# FPGA_IO.net
KiCad netlist of a schematic drawn in Altium Designer
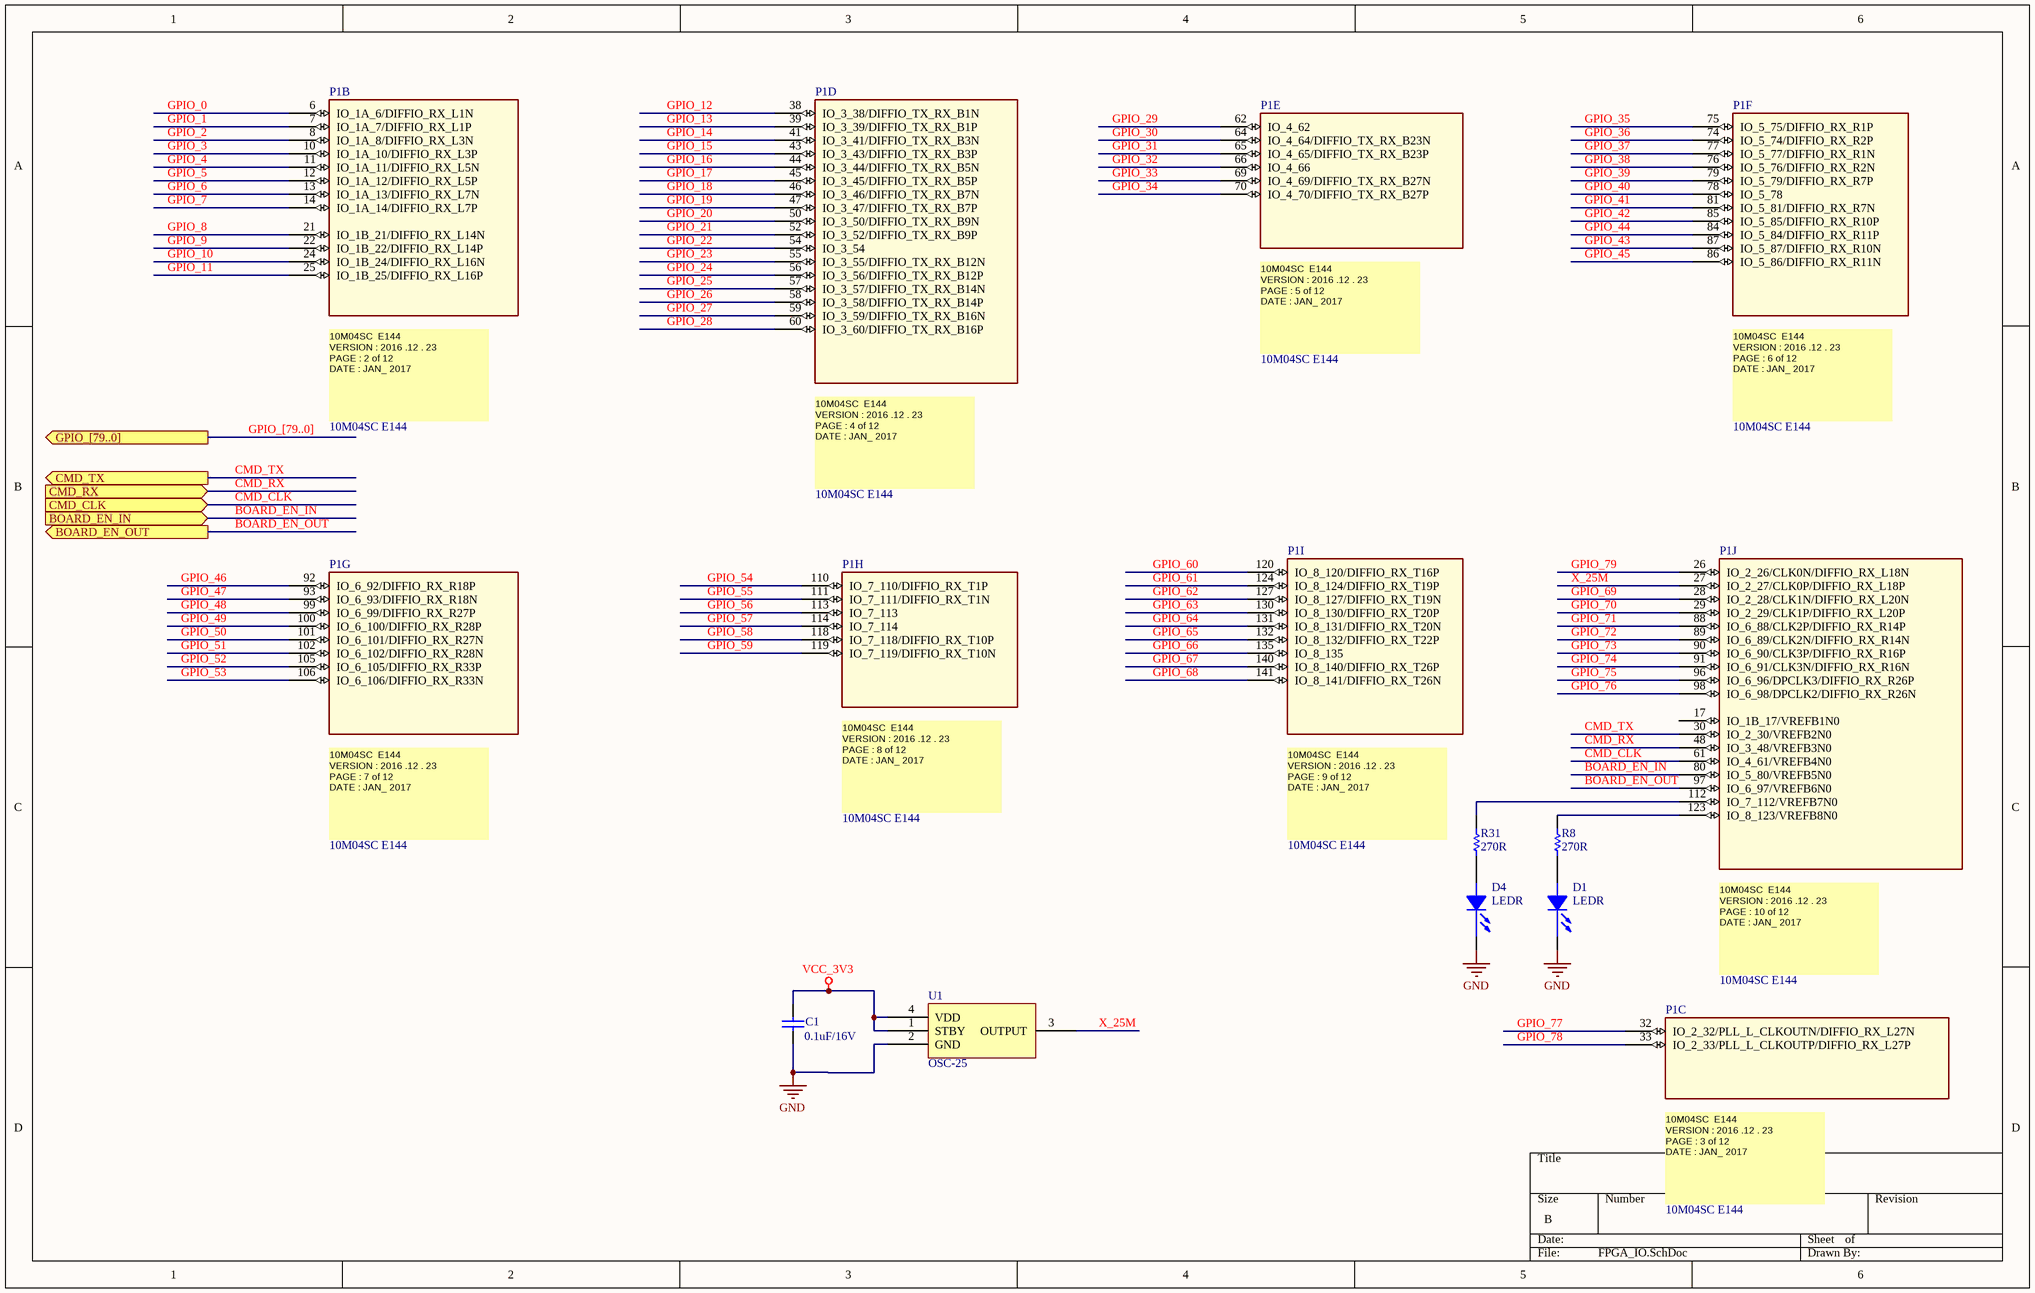
[diagram p0: FPGA_IO.SchDoc]

(export (version "E")
  (design (tool "Eeschema 10.0.6"))
  (components
    (comp (ref "C1")
      (value "0.1uF/16V")
      (footprint "0402_CAP")
      (description "Multilayer Ceramic Capacitors MLCC - SMD/SMT 10% AEC-Q200 16V 0.1uF X7R 0402")
      (fields
        (field (name "STOCKIEST PART NO") "80-C0402T104K4RACTU")
        (field (name "MFR PART NO") "C0402T104K4RACTU")
      )
      (libsource (lib "Miscellaneous Devices") (part "Cap"))
    )
    (comp (ref "D1")
      (value "LEDR")
      (footprint "LED0603")
      (description "Standard LEDs - SMD Red 631nm 14mcd 5mA")
      (fields (field (name "MANUFACTURER") "Lite-On") (field (name "STOCKIEST PART NO") "859-LTSTC193KRKT5A"))
      (libsource (lib "de20") (part "LED"))
    )
    (comp (ref "D4")
      (value "LEDR")
      (footprint "LED0603")
      (description "Standard LEDs - SMD Red 631nm 14mcd 5mA")
      (fields (field (name "MANUFACTURER") "Lite-On") (field (name "STOCKIEST PART NO") "859-LTSTC193KRKT5A"))
      (libsource (lib "de20") (part "LED"))
    )
    (comp (ref "P1") (value "10M04SC E144") (libsource (lib "10m04sc_Library") (part "10M04SC E144")))
    (comp (ref "R8")
      (value "270R")
      (footprint "AXIAL-0.3")
      (description "Resistor")
      (fields (field (name "PUBLISHER") "Altium Limited"))
      (libsource (lib "Miscellaneous Devices") (part "Res1"))
    )
    (comp (ref "R31")
      (value "270R")
      (footprint "AXIAL-0.3")
      (description "Resistor")
      (fields (field (name "PUBLISHER") "Altium Limited"))
      (libsource (lib "Miscellaneous Devices") (part "Res1"))
    )
    (comp (ref "U1")
      (value "OSC-25")
      (footprint "ASE-25.000MHZ-LC-T")
      (description "Standard Clock Oscillators 25.0 MHZ 3.3V 50PPM SMD 32")
      (fields
        (field (name "STOCKIEST PART NO") "815-ASE25.000MHZLCT")
        (field (name "MFR PART NO") "ASE-25.000MHZ-LC-T")
      )
      (libsource (lib "Schlib1") (part "CRYSTAL"))
    )
  )
  (nets
    (net (code "1") (name "/BOARD_EN_IN") (class "Default")
      (node (ref "P1") (pin "80") (pinfunction "IO_5_80/VREFB5N0_80") (pintype "bidirectional"))
    )
    (net (code "2") (name "/BOARD_EN_OUT") (class "Default")
      (node (ref "P1") (pin "97") (pinfunction "IO_6_97/VREFB6N0_97") (pintype "bidirectional"))
    )
    (net (code "3") (name "/CMD_CLK") (class "Default")
      (node (ref "P1") (pin "61") (pinfunction "IO_4_61/VREFB4N0_61") (pintype "bidirectional"))
    )
    (net (code "4") (name "/CMD_RX") (class "Default")
      (node (ref "P1") (pin "48") (pinfunction "IO_3_48/VREFB3N0_48") (pintype "bidirectional"))
    )
    (net (code "5") (name "/CMD_TX") (class "Default")
      (node (ref "P1") (pin "30") (pinfunction "IO_2_30/VREFB2N0_30") (pintype "bidirectional"))
    )
    (net (code "6") (name "/GPIO_0") (class "Default")
      (node (ref "P1") (pin "6") (pinfunction "IO_1A_6/DIFFIO_RX_L1N_6") (pintype "bidirectional"))
    )
    (net (code "7") (name "/GPIO_1") (class "Default")
      (node (ref "P1") (pin "7") (pinfunction "IO_1A_7/DIFFIO_RX_L1P_7") (pintype "bidirectional"))
    )
    (net (code "8") (name "/GPIO_2") (class "Default")
      (node (ref "P1") (pin "8") (pinfunction "IO_1A_8/DIFFIO_RX_L3N_8") (pintype "bidirectional"))
    )
    (net (code "9") (name "/GPIO_3") (class "Default")
      (node (ref "P1") (pin "10") (pinfunction "IO_1A_10/DIFFIO_RX_L3P_10") (pintype "bidirectional"))
    )
    (net (code "10") (name "/GPIO_4") (class "Default")
      (node (ref "P1") (pin "11") (pinfunction "IO_1A_11/DIFFIO_RX_L5N_11") (pintype "bidirectional"))
    )
    (net (code "11") (name "/GPIO_5") (class "Default")
      (node (ref "P1") (pin "12") (pinfunction "IO_1A_12/DIFFIO_RX_L5P_12") (pintype "bidirectional"))
    )
    (net (code "12") (name "/GPIO_6") (class "Default")
      (node (ref "P1") (pin "13") (pinfunction "IO_1A_13/DIFFIO_RX_L7N_13") (pintype "bidirectional"))
    )
    (net (code "13") (name "/GPIO_7") (class "Default")
      (node (ref "P1") (pin "14") (pinfunction "IO_1A_14/DIFFIO_RX_L7P_14") (pintype "bidirectional"))
    )
    (net (code "14") (name "/GPIO_8") (class "Default")
      (node (ref "P1") (pin "21") (pinfunction "IO_1B_21/DIFFIO_RX_L14N_21") (pintype "bidirectional"))
    )
    (net (code "15") (name "/GPIO_9") (class "Default")
      (node (ref "P1") (pin "22") (pinfunction "IO_1B_22/DIFFIO_RX_L14P_22") (pintype "bidirectional"))
    )
    (net (code "16") (name "/GPIO_10") (class "Default")
      (node (ref "P1") (pin "24") (pinfunction "IO_1B_24/DIFFIO_RX_L16N_24") (pintype "bidirectional"))
    )
    (net (code "17") (name "/GPIO_11") (class "Default")
      (node (ref "P1") (pin "25") (pinfunction "IO_1B_25/DIFFIO_RX_L16P_25") (pintype "bidirectional"))
    )
    (net (code "18") (name "/GPIO_12") (class "Default")
      (node (ref "P1") (pin "38") (pinfunction "IO_3_38/DIFFIO_TX_RX_B1N_38") (pintype "bidirectional"))
    )
    (net (code "19") (name "/GPIO_13") (class "Default")
      (node (ref "P1") (pin "39") (pinfunction "IO_3_39/DIFFIO_TX_RX_B1P_39") (pintype "bidirectional"))
    )
    (net (code "20") (name "/GPIO_14") (class "Default")
      (node (ref "P1") (pin "41") (pinfunction "IO_3_41/DIFFIO_TX_RX_B3N_41") (pintype "bidirectional"))
    )
    (net (code "21") (name "/GPIO_15") (class "Default")
      (node (ref "P1") (pin "43") (pinfunction "IO_3_43/DIFFIO_TX_RX_B3P_43") (pintype "bidirectional"))
    )
    (net (code "22") (name "/GPIO_16") (class "Default")
      (node (ref "P1") (pin "44") (pinfunction "IO_3_44/DIFFIO_TX_RX_B5N_44") (pintype "bidirectional"))
    )
    (net (code "23") (name "/GPIO_17") (class "Default")
      (node (ref "P1") (pin "45") (pinfunction "IO_3_45/DIFFIO_TX_RX_B5P_45") (pintype "bidirectional"))
    )
    (net (code "24") (name "/GPIO_18") (class "Default")
      (node (ref "P1") (pin "46") (pinfunction "IO_3_46/DIFFIO_TX_RX_B7N_46") (pintype "bidirectional"))
    )
    (net (code "25") (name "/GPIO_19") (class "Default")
      (node (ref "P1") (pin "47") (pinfunction "IO_3_47/DIFFIO_TX_RX_B7P_47") (pintype "bidirectional"))
    )
    (net (code "26") (name "/GPIO_20") (class "Default")
      (node (ref "P1") (pin "50") (pinfunction "IO_3_50/DIFFIO_TX_RX_B9N_50") (pintype "bidirectional"))
    )
    (net (code "27") (name "/GPIO_21") (class "Default")
      (node (ref "P1") (pin "52") (pinfunction "IO_3_52/DIFFIO_TX_RX_B9P_52") (pintype "bidirectional"))
    )
    (net (code "28") (name "/GPIO_22") (class "Default")
      (node (ref "P1") (pin "54") (pinfunction "IO_3_54_54") (pintype "bidirectional"))
    )
    (net (code "29") (name "/GPIO_23") (class "Default")
      (node (ref "P1") (pin "55") (pinfunction "IO_3_55/DIFFIO_TX_RX_B12N_55") (pintype "bidirectional"))
    )
    (net (code "30") (name "/GPIO_24") (class "Default")
      (node (ref "P1") (pin "56") (pinfunction "IO_3_56/DIFFIO_TX_RX_B12P_56") (pintype "bidirectional"))
    )
    (net (code "31") (name "/GPIO_25") (class "Default")
      (node (ref "P1") (pin "57") (pinfunction "IO_3_57/DIFFIO_TX_RX_B14N_57") (pintype "bidirectional"))
    )
    (net (code "32") (name "/GPIO_26") (class "Default")
      (node (ref "P1") (pin "58") (pinfunction "IO_3_58/DIFFIO_TX_RX_B14P_58") (pintype "bidirectional"))
    )
    (net (code "33") (name "/GPIO_27") (class "Default")
      (node (ref "P1") (pin "59") (pinfunction "IO_3_59/DIFFIO_TX_RX_B16N_59") (pintype "bidirectional"))
    )
    (net (code "34") (name "/GPIO_28") (class "Default")
      (node (ref "P1") (pin "60") (pinfunction "IO_3_60/DIFFIO_TX_RX_B16P_60") (pintype "bidirectional"))
    )
    (net (code "35") (name "/GPIO_29") (class "Default")
      (node (ref "P1") (pin "62") (pinfunction "IO_4_62_62") (pintype "bidirectional"))
    )
    (net (code "36") (name "/GPIO_30") (class "Default")
      (node (ref "P1") (pin "64") (pinfunction "IO_4_64/DIFFIO_TX_RX_B23N_64") (pintype "bidirectional"))
    )
    (net (code "37") (name "/GPIO_31") (class "Default")
      (node (ref "P1") (pin "65") (pinfunction "IO_4_65/DIFFIO_TX_RX_B23P_65") (pintype "bidirectional"))
    )
    (net (code "38") (name "/GPIO_32") (class "Default")
      (node (ref "P1") (pin "66") (pinfunction "IO_4_66_66") (pintype "bidirectional"))
    )
    (net (code "39") (name "/GPIO_33") (class "Default")
      (node (ref "P1") (pin "69") (pinfunction "IO_4_69/DIFFIO_TX_RX_B27N_69") (pintype "bidirectional"))
    )
    (net (code "40") (name "/GPIO_34") (class "Default")
      (node (ref "P1") (pin "70") (pinfunction "IO_4_70/DIFFIO_TX_RX_B27P_70") (pintype "bidirectional"))
    )
    (net (code "41") (name "/GPIO_35") (class "Default")
      (node (ref "P1") (pin "75") (pinfunction "IO_5_75/DIFFIO_RX_R1P_75") (pintype "bidirectional"))
    )
    (net (code "42") (name "/GPIO_36") (class "Default")
      (node (ref "P1") (pin "74") (pinfunction "IO_5_74/DIFFIO_RX_R2P_74") (pintype "bidirectional"))
    )
    (net (code "43") (name "/GPIO_37") (class "Default")
      (node (ref "P1") (pin "77") (pinfunction "IO_5_77/DIFFIO_RX_R1N_77") (pintype "bidirectional"))
    )
    (net (code "44") (name "/GPIO_38") (class "Default")
      (node (ref "P1") (pin "76") (pinfunction "IO_5_76/DIFFIO_RX_R2N_76") (pintype "bidirectional"))
    )
    (net (code "45") (name "/GPIO_39") (class "Default")
      (node (ref "P1") (pin "79") (pinfunction "IO_5_79/DIFFIO_RX_R7P_79") (pintype "bidirectional"))
    )
    (net (code "46") (name "/GPIO_40") (class "Default")
      (node (ref "P1") (pin "78") (pinfunction "IO_5_78_78") (pintype "bidirectional"))
    )
    (net (code "47") (name "/GPIO_41") (class "Default")
      (node (ref "P1") (pin "81") (pinfunction "IO_5_81/DIFFIO_RX_R7N_81") (pintype "bidirectional"))
    )
    (net (code "48") (name "/GPIO_42") (class "Default")
      (node (ref "P1") (pin "85") (pinfunction "IO_5_85/DIFFIO_RX_R10P_85") (pintype "bidirectional"))
    )
    (net (code "49") (name "/GPIO_43") (class "Default")
      (node (ref "P1") (pin "87") (pinfunction "IO_5_87/DIFFIO_RX_R10N_87") (pintype "bidirectional"))
    )
    (net (code "50") (name "/GPIO_44") (class "Default")
      (node (ref "P1") (pin "84") (pinfunction "IO_5_84/DIFFIO_RX_R11P_84") (pintype "bidirectional"))
    )
    (net (code "51") (name "/GPIO_45") (class "Default")
      (node (ref "P1") (pin "86") (pinfunction "IO_5_86/DIFFIO_RX_R11N_86") (pintype "bidirectional"))
    )
    (net (code "52") (name "/GPIO_46") (class "Default")
      (node (ref "P1") (pin "92") (pinfunction "IO_6_92/DIFFIO_RX_R18P_92") (pintype "bidirectional"))
    )
    (net (code "53") (name "/GPIO_47") (class "Default")
      (node (ref "P1") (pin "93") (pinfunction "IO_6_93/DIFFIO_RX_R18N_93") (pintype "bidirectional"))
    )
    (net (code "54") (name "/GPIO_48") (class "Default")
      (node (ref "P1") (pin "99") (pinfunction "IO_6_99/DIFFIO_RX_R27P_99") (pintype "bidirectional"))
    )
    (net (code "55") (name "/GPIO_49") (class "Default")
      (node (ref "P1") (pin "100") (pinfunction "IO_6_100/DIFFIO_RX_R28P_100") (pintype "bidirectional"))
    )
    (net (code "56") (name "/GPIO_50") (class "Default")
      (node (ref "P1") (pin "101") (pinfunction "IO_6_101/DIFFIO_RX_R27N_101") (pintype "bidirectional"))
    )
    (net (code "57") (name "/GPIO_51") (class "Default")
      (node (ref "P1") (pin "102") (pinfunction "IO_6_102/DIFFIO_RX_R28N_102") (pintype "bidirectional"))
    )
    (net (code "58") (name "/GPIO_52") (class "Default")
      (node (ref "P1") (pin "105") (pinfunction "IO_6_105/DIFFIO_RX_R33P_105") (pintype "bidirectional"))
    )
    (net (code "59") (name "/GPIO_53") (class "Default")
      (node (ref "P1") (pin "106") (pinfunction "IO_6_106/DIFFIO_RX_R33N_106") (pintype "bidirectional"))
    )
    (net (code "60") (name "/GPIO_54") (class "Default")
      (node (ref "P1") (pin "110") (pinfunction "IO_7_110/DIFFIO_RX_T1P_110") (pintype "bidirectional"))
    )
    (net (code "61") (name "/GPIO_55") (class "Default")
      (node (ref "P1") (pin "111") (pinfunction "IO_7_111/DIFFIO_RX_T1N_111") (pintype "bidirectional"))
    )
    (net (code "62") (name "/GPIO_56") (class "Default")
      (node (ref "P1") (pin "113") (pinfunction "IO_7_113_113") (pintype "bidirectional"))
    )
    (net (code "63") (name "/GPIO_57") (class "Default")
      (node (ref "P1") (pin "114") (pinfunction "IO_7_114_114") (pintype "bidirectional"))
    )
    (net (code "64") (name "/GPIO_58") (class "Default")
      (node (ref "P1") (pin "118") (pinfunction "IO_7_118/DIFFIO_RX_T10P_118") (pintype "bidirectional"))
    )
    (net (code "65") (name "/GPIO_59") (class "Default")
      (node (ref "P1") (pin "119") (pinfunction "IO_7_119/DIFFIO_RX_T10N_119") (pintype "bidirectional"))
    )
    (net (code "66") (name "/GPIO_60") (class "Default")
      (node (ref "P1") (pin "120") (pinfunction "IO_8_120/DIFFIO_RX_T16P_120") (pintype "bidirectional"))
    )
    (net (code "67") (name "/GPIO_61") (class "Default")
      (node (ref "P1") (pin "124") (pinfunction "IO_8_124/DIFFIO_RX_T19P_124") (pintype "bidirectional"))
    )
    (net (code "68") (name "/GPIO_62") (class "Default")
      (node (ref "P1") (pin "127") (pinfunction "IO_8_127/DIFFIO_RX_T19N_127") (pintype "bidirectional"))
    )
    (net (code "69") (name "/GPIO_63") (class "Default")
      (node (ref "P1") (pin "130") (pinfunction "IO_8_130/DIFFIO_RX_T20P_130") (pintype "bidirectional"))
    )
    (net (code "70") (name "/GPIO_64") (class "Default")
      (node (ref "P1") (pin "131") (pinfunction "IO_8_131/DIFFIO_RX_T20N_131") (pintype "bidirectional"))
    )
    (net (code "71") (name "/GPIO_65") (class "Default")
      (node (ref "P1") (pin "132") (pinfunction "IO_8_132/DIFFIO_RX_T22P_132") (pintype "bidirectional"))
    )
    (net (code "72") (name "/GPIO_66") (class "Default")
      (node (ref "P1") (pin "135") (pinfunction "IO_8_135_135") (pintype "bidirectional"))
    )
    (net (code "73") (name "/GPIO_67") (class "Default")
      (node (ref "P1") (pin "140") (pinfunction "IO_8_140/DIFFIO_RX_T26P_140") (pintype "bidirectional"))
    )
    (net (code "74") (name "/GPIO_68") (class "Default")
      (node (ref "P1") (pin "141") (pinfunction "IO_8_141/DIFFIO_RX_T26N_141") (pintype "bidirectional"))
    )
    (net (code "75") (name "/GPIO_69") (class "Default")
      (node (ref "P1") (pin "28") (pinfunction "IO_2_28/CLK1N/DIFFIO_RX_L20N_28") (pintype "bidirectional"))
    )
    (net (code "76") (name "/GPIO_70") (class "Default")
      (node (ref "P1") (pin "29") (pinfunction "IO_2_29/CLK1P/DIFFIO_RX_L20P_29") (pintype "bidirectional"))
    )
    (net (code "77") (name "/GPIO_71") (class "Default")
      (node (ref "P1") (pin "88") (pinfunction "IO_6_88/CLK2P/DIFFIO_RX_R14P_88") (pintype "bidirectional"))
    )
    (net (code "78") (name "/GPIO_72") (class "Default")
      (node (ref "P1") (pin "89") (pinfunction "IO_6_89/CLK2N/DIFFIO_RX_R14N_89") (pintype "bidirectional"))
    )
    (net (code "79") (name "/GPIO_73") (class "Default")
      (node (ref "P1") (pin "90") (pinfunction "IO_6_90/CLK3P/DIFFIO_RX_R16P_90") (pintype "bidirectional"))
    )
    (net (code "80") (name "/GPIO_74") (class "Default")
      (node (ref "P1") (pin "91") (pinfunction "IO_6_91/CLK3N/DIFFIO_RX_R16N_91") (pintype "bidirectional"))
    )
    (net (code "81") (name "/GPIO_75") (class "Default")
      (node (ref "P1") (pin "96") (pinfunction "IO_6_96/DPCLK3/DIFFIO_RX_R26P_96") (pintype "bidirectional"))
    )
    (net (code "82") (name "/GPIO_76") (class "Default")
      (node (ref "P1") (pin "98") (pinfunction "IO_6_98/DPCLK2/DIFFIO_RX_R26N_98") (pintype "bidirectional"))
    )
    (net (code "83") (name "/GPIO_77") (class "Default")
      (node (ref "P1") (pin "32") (pinfunction "IO_2_32/PLL_L_CLKOUTN/DIFFIO_RX_L27N_32") (pintype "bidirectional"))
    )
    (net (code "84") (name "/GPIO_78") (class "Default")
      (node (ref "P1") (pin "33") (pinfunction "IO_2_33/PLL_L_CLKOUTP/DIFFIO_RX_L27P_33") (pintype "bidirectional"))
    )
    (net (code "85") (name "/GPIO_79") (class "Default")
      (node (ref "P1") (pin "26") (pinfunction "IO_2_26/CLK0N/DIFFIO_RX_L18N_26") (pintype "bidirectional"))
    )
    (net (code "87") (name "/X_25M") (class "Default")
      (node (ref "P1") (pin "27") (pinfunction "IO_2_27/CLK0P/DIFFIO_RX_L18P_27") (pintype "bidirectional"))
      (node (ref "U1") (pin "3") (pinfunction "OUTPUT_3") (pintype "passive"))
    )
    (net (code "88") (name "GND") (class "Default")
      (node (ref "C1") (pin "1") (pinfunction "1_1") (pintype "passive"))
      (node (ref "D1") (pin "2") (pinfunction "CATHODE_2") (pintype "passive"))
      (node (ref "D4") (pin "2") (pinfunction "CATHODE_2") (pintype "passive"))
      (node (ref "U1") (pin "2") (pinfunction "GND_2") (pintype "passive"))
    )
    (net (code "89") (name "Net-(D1-ANODE)") (class "Default")
      (node (ref "D1") (pin "1") (pinfunction "ANODE_1") (pintype "passive"))
      (node (ref "R8") (pin "1") (pinfunction "1_1") (pintype "passive"))
    )
    (net (code "90") (name "Net-(D4-ANODE)") (class "Default")
      (node (ref "D4") (pin "1") (pinfunction "ANODE_1") (pintype "passive"))
      (node (ref "R31") (pin "1") (pinfunction "1_1") (pintype "passive"))
    )
    (net (code "91") (name "Net-(P1J-IO_7_112{slash}VREFB7N0)") (class "Default")
      (node (ref "P1") (pin "112") (pinfunction "IO_7_112/VREFB7N0_112") (pintype "bidirectional"))
      (node (ref "R31") (pin "2") (pinfunction "2_2") (pintype "passive"))
    )
    (net (code "92") (name "Net-(P1J-IO_8_123{slash}VREFB8N0)") (class "Default")
      (node (ref "P1") (pin "123") (pinfunction "IO_8_123/VREFB8N0_123") (pintype "bidirectional"))
      (node (ref "R8") (pin "2") (pinfunction "2_2") (pintype "passive"))
    )
    (net (code "93") (name "VCC_3V3") (class "Default")
      (node (ref "C1") (pin "2") (pinfunction "2_2") (pintype "passive"))
      (node (ref "U1") (pin "1") (pinfunction "STBY_1") (pintype "passive"))
      (node (ref "U1") (pin "4") (pinfunction "VDD_4") (pintype "passive"))
    )
    (net (code "94") (name "unconnected-(P1J-IO_1B_17{slash}VREFB1N0-Pad17)") (class "Default")
      (node (ref "P1") (pin "17") (pinfunction "IO_1B_17/VREFB1N0_17") (pintype "bidirectional"))
    )
  )
)
